# Four-leg_robot.net
KiCad netlist of a schematic drawn in Altium Designer
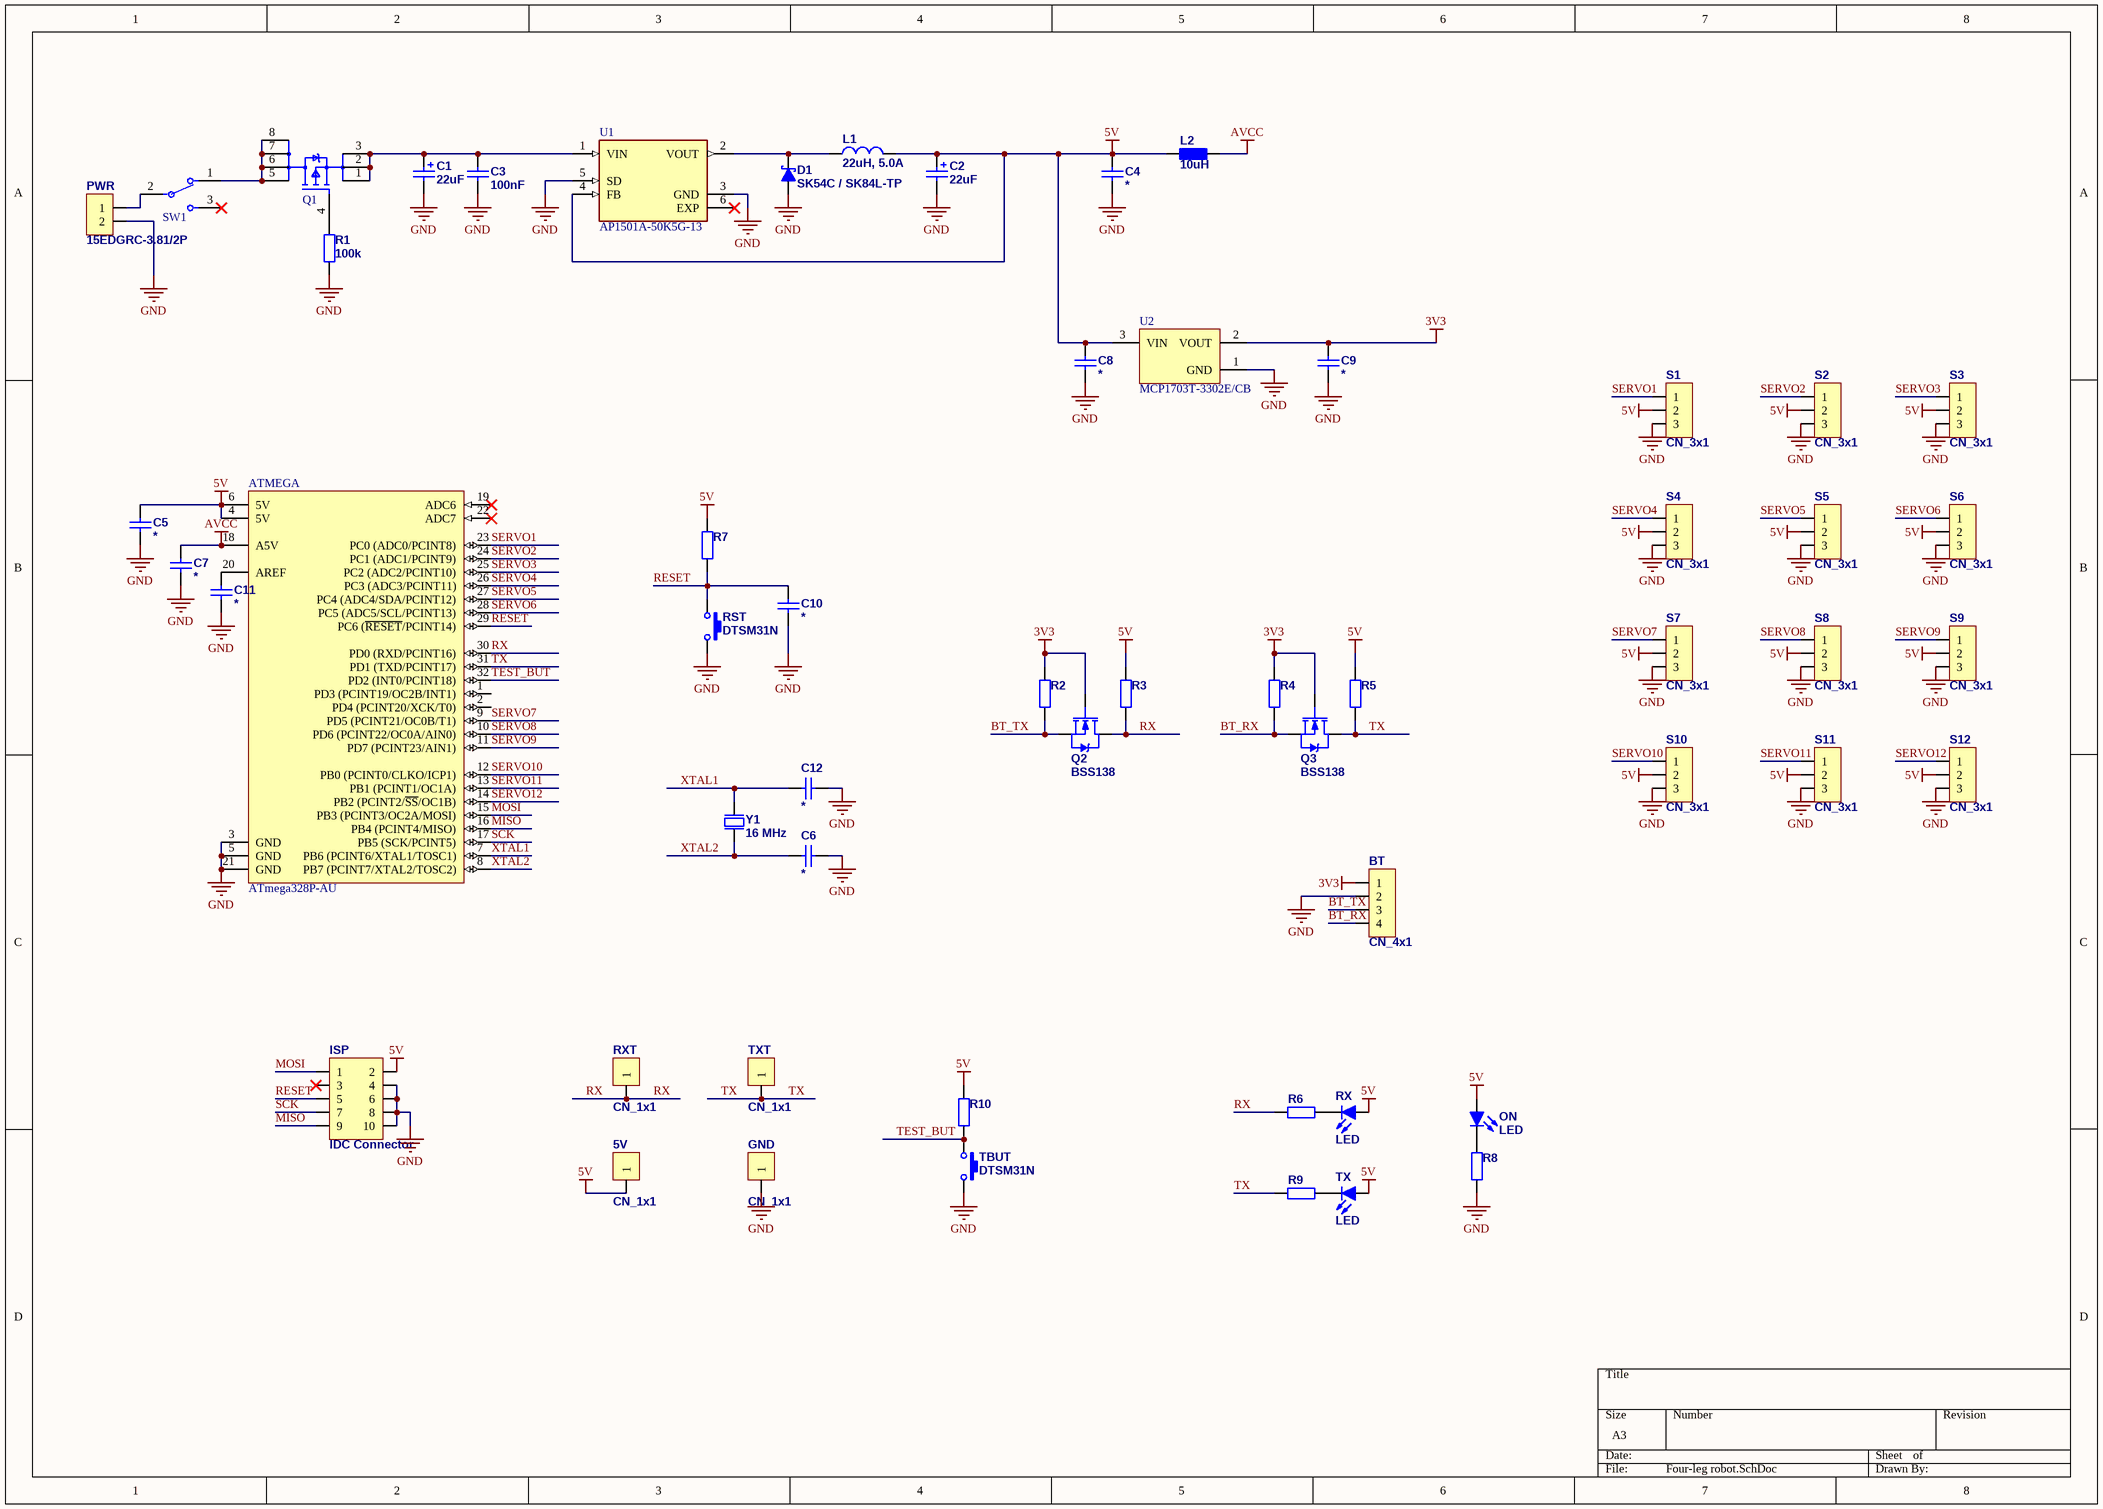
[diagram p0: Four-leg robot.SchDoc]

(export (version "E")
  (design (tool "Eeschema 10.0.6"))
  (components
    (comp (ref "5V") (value "CN_1x1") (footprint "GP_1x1") (libsource (lib "goldpin_male") (part "CN_1x1")))
    (comp (ref "ATMEGA")
      (value "ATmega328P-AU")
      (footprint "32A_N")
      (libsource (lib "Atmel Microcontroller megaAVR") (part "ATmega328P-AU"))
    )
    (comp (ref "BT")
      (value "CN_4x1")
      (footprint "GP_4x1_F")
      (libsource (lib "goldpin_female") (part "CN_4x1"))
    )
    (comp (ref "C1")
      (value "22uF")
      (footprint "SMDB")
      (description "Polarized Tantalum Capacitor")
      (libsource (lib "capacitors") (part "Cap Pol Tant"))
    )
    (comp (ref "C2")
      (value "22uF")
      (footprint "SMDB")
      (description "Polarized Tantalum Capacitor")
      (libsource (lib "capacitors") (part "Cap Pol Tant"))
    )
    (comp (ref "C3")
      (value "100nF")
      (footprint "C0805")
      (description "Capacitor")
      (libsource (lib "capacitors") (part "Cap"))
    )
    (comp (ref "C4")
      (value "*")
      (footprint "C0805")
      (description "Capacitor")
      (fields (field (name "ALTIUM_VALUE") "*"))
      (libsource (lib "capacitors") (part "Cap"))
    )
    (comp (ref "C5")
      (value "*")
      (footprint "C0805")
      (description "Capacitor")
      (fields (field (name "ALTIUM_VALUE") "*"))
      (libsource (lib "capacitors") (part "Cap"))
    )
    (comp (ref "C6")
      (value "*")
      (footprint "C0805")
      (description "Capacitor")
      (fields (field (name "ALTIUM_VALUE") "*"))
      (libsource (lib "capacitors") (part "Cap"))
    )
    (comp (ref "C7")
      (value "*")
      (footprint "C0805")
      (description "Capacitor")
      (fields (field (name "ALTIUM_VALUE") "*"))
      (libsource (lib "capacitors") (part "Cap"))
    )
    (comp (ref "C8")
      (value "*")
      (footprint "C0805")
      (description "Capacitor")
      (fields (field (name "ALTIUM_VALUE") "*"))
      (libsource (lib "capacitors") (part "Cap"))
    )
    (comp (ref "C9")
      (value "*")
      (footprint "C0805")
      (description "Capacitor")
      (fields (field (name "ALTIUM_VALUE") "*"))
      (libsource (lib "capacitors") (part "Cap"))
    )
    (comp (ref "C10")
      (value "*")
      (footprint "C0805")
      (description "Capacitor")
      (fields (field (name "ALTIUM_VALUE") "*"))
      (libsource (lib "capacitors") (part "Cap"))
    )
    (comp (ref "C11")
      (value "*")
      (footprint "C0805")
      (description "Capacitor")
      (fields (field (name "ALTIUM_VALUE") "*"))
      (libsource (lib "capacitors") (part "Cap"))
    )
    (comp (ref "C12")
      (value "*")
      (footprint "C0805")
      (description "Capacitor")
      (fields (field (name "ALTIUM_VALUE") "*"))
      (libsource (lib "capacitors") (part "Cap"))
    )
    (comp (ref "D1")
      (value "SK54C / SK84L-TP")
      (footprint "SMC")
      (description "Schottky Diode: 40V, 5A")
      (libsource (lib "diodes_schottky") (part "SK54C"))
    )
    (comp (ref "GND") (value "CN_1x1") (footprint "GP_1x1") (libsource (lib "goldpin_male") (part "CN_1x1")))
    (comp (ref "ISP") (value "IDC Connector") (footprint "IDC10") (libsource (lib "idc") (part "CN_5x2")))
    (comp (ref "L1")
      (value "22uH, 5.0A")
      (footprint "DE1209")
      (description "DE1209-22")
      (libsource (lib "inductors") (part "DE1209-22"))
    )
    (comp (ref "L2")
      (value "10uH")
      (footprint "L0805")
      (description "Inductor")
      (libsource (lib "inductors") (part "Ind2"))
    )
    (comp (ref "ON")
      (value "LED")
      (footprint "LED0805G")
      (description "Typical RED, GREEN, YELLOW, AMBER GaAs LED")
      (libsource (lib "leds") (part "LED"))
    )
    (comp (ref "PWR")
      (value "15EDGRC-3.81/2P")
      (footprint "15EDGRC-3.81/2P_WO_CN")
      (description "Degson 7A, 250V, 2 Pole Plug-in Terminal Block")
      (libsource (lib "terminal_blocks") (part "15EDGRC-3.81/2P"))
    )
    (comp (ref "Q1")
      (value "IRF7425PBF")
      (footprint "Infineon_PG-DSO-8_MFG")
      (libsource (lib "Trans_Infineon_IRF7425PBF_eec") (part "IRF7425PBF"))
    )
    (comp (ref "Q2")
      (value "BSS138")
      (footprint "SOT-23")
      (description "N-Channel Enhancement Mode Vertical DMOS FET")
      (fields (field (name "PUBLISHER") "Altium Limited"))
      (libsource (lib "transistors_mos") (part "BSS138"))
    )
    (comp (ref "Q3")
      (value "BSS138")
      (footprint "SOT-23")
      (description "N-Channel Enhancement Mode Vertical DMOS FET")
      (fields (field (name "PUBLISHER") "Altium Limited"))
      (libsource (lib "transistors_mos") (part "BSS138"))
    )
    (comp (ref "R1")
      (value "100k")
      (footprint "R0805")
      (description "Resistor")
      (libsource (lib "resistors") (part "Res"))
    )
    (comp (ref "R2")
      (value "~")
      (footprint "R0805")
      (description "Resistor")
      (libsource (lib "resistors") (part "Res"))
    )
    (comp (ref "R3")
      (value "~")
      (footprint "R0805")
      (description "Resistor")
      (libsource (lib "resistors") (part "Res"))
    )
    (comp (ref "R4")
      (value "~")
      (footprint "R0805")
      (description "Resistor")
      (libsource (lib "resistors") (part "Res"))
    )
    (comp (ref "R5")
      (value "~")
      (footprint "R0805")
      (description "Resistor")
      (libsource (lib "resistors") (part "Res"))
    )
    (comp (ref "R6")
      (value "~")
      (footprint "R0805")
      (description "Resistor")
      (libsource (lib "") (part "Res_1"))
    )
    (comp (ref "R7")
      (value "~")
      (footprint "R0805")
      (description "Resistor")
      (libsource (lib "resistors") (part "Res"))
    )
    (comp (ref "R8")
      (value "~")
      (footprint "R0805")
      (description "Resistor")
      (libsource (lib "resistors") (part "Res"))
    )
    (comp (ref "R9")
      (value "~")
      (footprint "R0805")
      (description "Resistor")
      (libsource (lib "") (part "Res_1"))
    )
    (comp (ref "R10")
      (value "~")
      (footprint "R0805")
      (description "Resistor")
      (libsource (lib "resistors") (part "Res"))
    )
    (comp (ref "RST")
      (value "DTSM31N")
      (footprint "DTSM-3")
      (description "DIPTRONICS 6x3,5mm SMD Tactile SPST-NO Switch")
      (libsource (lib "microswitches") (part "DTSM31N"))
    )
    (comp (ref "RX")
      (value "LED")
      (footprint "LED0805G")
      (description "Typical RED, GREEN, YELLOW, AMBER GaAs LED")
      (libsource (lib "leds") (part "LED"))
    )
    (comp (ref "RXT") (value "CN_1x1") (footprint "GP_1x1") (libsource (lib "goldpin_male") (part "CN_1x1")))
    (comp (ref "S1") (value "CN_3x1") (footprint "GP_3x1") (libsource (lib "goldpin_male") (part "CN_3x1")))
    (comp (ref "S2") (value "CN_3x1") (footprint "GP_3x1") (libsource (lib "goldpin_male") (part "CN_3x1")))
    (comp (ref "S3") (value "CN_3x1") (footprint "GP_3x1") (libsource (lib "goldpin_male") (part "CN_3x1")))
    (comp (ref "S4") (value "CN_3x1") (footprint "GP_3x1") (libsource (lib "goldpin_male") (part "CN_3x1")))
    (comp (ref "S5") (value "CN_3x1") (footprint "GP_3x1") (libsource (lib "goldpin_male") (part "CN_3x1")))
    (comp (ref "S6") (value "CN_3x1") (footprint "GP_3x1") (libsource (lib "goldpin_male") (part "CN_3x1")))
    (comp (ref "S7") (value "CN_3x1") (footprint "GP_3x1") (libsource (lib "goldpin_male") (part "CN_3x1")))
    (comp (ref "S8") (value "CN_3x1") (footprint "GP_3x1") (libsource (lib "goldpin_male") (part "CN_3x1")))
    (comp (ref "S9") (value "CN_3x1") (footprint "GP_3x1") (libsource (lib "goldpin_male") (part "CN_3x1")))
    (comp (ref "S10") (value "CN_3x1") (footprint "GP_3x1") (libsource (lib "goldpin_male") (part "CN_3x1")))
    (comp (ref "S11") (value "CN_3x1") (footprint "GP_3x1") (libsource (lib "goldpin_male") (part "CN_3x1")))
    (comp (ref "S12") (value "CN_3x1") (footprint "GP_3x1") (libsource (lib "goldpin_male") (part "CN_3x1")))
    (comp (ref "SW1")
      (value "Switch_C&K_1101M2S3CQE2_eec")
      (footprint "C&K_1101M2S3CQE2_0")
      (description "SWITCH SLIDE SPDT 6A 120V")
      (fields (field (name "PART NUMBER") "1101M2S3CQE2") (field (name "MANUFACTURER") "C&K"))
      (libsource (lib "Switch_C&K_1101M2S3CQE2_eec") (part "Switch_C&K_1101M2S3CQE2_eec"))
    )
    (comp (ref "TBUT")
      (value "DTSM31N")
      (footprint "DTSM-3")
      (description "DIPTRONICS 6x3,5mm SMD Tactile SPST-NO Switch")
      (libsource (lib "microswitches") (part "DTSM31N"))
    )
    (comp (ref "TX")
      (value "LED")
      (footprint "LED0805G")
      (description "Typical RED, GREEN, YELLOW, AMBER GaAs LED")
      (libsource (lib "leds") (part "LED"))
    )
    (comp (ref "TXT") (value "CN_1x1") (footprint "GP_1x1") (libsource (lib "goldpin_male") (part "CN_1x1")))
    (comp (ref "U1")
      (value "AP1501A-50K5G-13")
      (footprint "TO-263-5:TO-263-5")
      (description "Voltage stabiliser; PMIC; 5A; TO263-5; SMD; buck; -20Ã·85Â°C; 800pcs.")
      (libsource (lib "AP1501A-33K5G-13") (part "AP1501A-33K5G-13"))
    )
    (comp (ref "U2")
      (value "MCP1703T-3302E/CB")
      (footprint "SOT-23")
      (libsource (lib "Microchip_MCP1703T_3302E_CB") (part "MCP1703T-3302E/CB"))
    )
    (comp (ref "Y1")
      (value "16 MHz")
      (footprint "HC49-S")
      (description "Crystal Oscillator")
      (libsource (lib "quartz_crystals_and_filters") (part "XTAL_2PIN"))
    )
  )
  (nets
    (net (code "1") (name "/BT_RX") (class "Default")
      (node (ref "BT") (pin "4") (pinfunction "4_4") (pintype "passive"))
      (node (ref "Q3") (pin "2") (pinfunction "S_2") (pintype "passive"))
      (node (ref "R4") (pin "1") (pinfunction "1_1") (pintype "passive"))
    )
    (net (code "2") (name "/BT_TX") (class "Default")
      (node (ref "BT") (pin "3") (pinfunction "3_3") (pintype "passive"))
      (node (ref "Q2") (pin "2") (pinfunction "S_2") (pintype "passive"))
      (node (ref "R2") (pin "1") (pinfunction "1_1") (pintype "passive"))
    )
    (net (code "3") (name "/MISO") (class "Default")
      (node (ref "ATMEGA") (pin "16") (pinfunction "PB4_(PCINT4/MISO)_16") (pintype "bidirectional"))
      (node (ref "ISP") (pin "9") (pinfunction "9_9") (pintype "passive"))
    )
    (net (code "4") (name "/MOSI") (class "Default")
      (node (ref "ATMEGA") (pin "15") (pinfunction "PB3_(PCINT3/OC2A/MOSI)_15") (pintype "bidirectional"))
      (node (ref "ISP") (pin "1") (pinfunction "1_1") (pintype "passive"))
    )
    (net (code "5") (name "/RESET") (class "Default")
      (node (ref "ATMEGA") (pin "29") (pinfunction "PC6_(~{RESET}/PCINT14)_29") (pintype "bidirectional"))
      (node (ref "C10") (pin "2") (pinfunction "2_2") (pintype "passive"))
      (node (ref "ISP") (pin "5") (pinfunction "5_5") (pintype "passive"))
      (node (ref "R7") (pin "1") (pinfunction "1_1") (pintype "passive"))
      (node (ref "RST") (pin "1") (pinfunction "1_1") (pintype "passive"))
    )
    (net (code "6") (name "/RX") (class "Default")
      (node (ref "ATMEGA") (pin "30") (pinfunction "PD0_(RXD/PCINT16)_30") (pintype "bidirectional"))
      (node (ref "Q2") (pin "3") (pinfunction "D_3") (pintype "passive"))
      (node (ref "R3") (pin "1") (pinfunction "1_1") (pintype "passive"))
      (node (ref "R6") (pin "1") (pinfunction "1_1") (pintype "passive"))
      (node (ref "RXT") (pin "1") (pinfunction "1_1") (pintype "passive"))
    )
    (net (code "7") (name "/SCK") (class "Default")
      (node (ref "ATMEGA") (pin "17") (pinfunction "PB5_(SCK/PCINT5)_17") (pintype "bidirectional"))
      (node (ref "ISP") (pin "7") (pinfunction "7_7") (pintype "passive"))
    )
    (net (code "8") (name "/SERVO1") (class "Default")
      (node (ref "ATMEGA") (pin "23") (pinfunction "PC0_(ADC0/PCINT8)_23") (pintype "bidirectional"))
      (node (ref "S1") (pin "1") (pinfunction "1_1") (pintype "passive"))
    )
    (net (code "9") (name "/SERVO2") (class "Default")
      (node (ref "ATMEGA") (pin "24") (pinfunction "PC1_(ADC1/PCINT9)_24") (pintype "bidirectional"))
      (node (ref "S2") (pin "1") (pinfunction "1_1") (pintype "passive"))
    )
    (net (code "10") (name "/SERVO3") (class "Default")
      (node (ref "ATMEGA") (pin "25") (pinfunction "PC2_(ADC2/PCINT10)_25") (pintype "bidirectional"))
      (node (ref "S3") (pin "1") (pinfunction "1_1") (pintype "passive"))
    )
    (net (code "11") (name "/SERVO4") (class "Default")
      (node (ref "ATMEGA") (pin "26") (pinfunction "PC3_(ADC3/PCINT11)_26") (pintype "bidirectional"))
      (node (ref "S4") (pin "1") (pinfunction "1_1") (pintype "passive"))
    )
    (net (code "12") (name "/SERVO5") (class "Default")
      (node (ref "ATMEGA") (pin "27") (pinfunction "PC4_(ADC4/SDA/PCINT12)_27") (pintype "bidirectional"))
      (node (ref "S5") (pin "1") (pinfunction "1_1") (pintype "passive"))
    )
    (net (code "13") (name "/SERVO6") (class "Default")
      (node (ref "ATMEGA") (pin "28") (pinfunction "PC5_(ADC5/SCL/PCINT13)_28") (pintype "bidirectional"))
      (node (ref "S6") (pin "1") (pinfunction "1_1") (pintype "passive"))
    )
    (net (code "14") (name "/SERVO7") (class "Default")
      (node (ref "ATMEGA") (pin "9") (pinfunction "PD5_(PCINT21/OC0B/T1)_9") (pintype "bidirectional"))
      (node (ref "S7") (pin "1") (pinfunction "1_1") (pintype "passive"))
    )
    (net (code "15") (name "/SERVO8") (class "Default")
      (node (ref "ATMEGA") (pin "10") (pinfunction "PD6_(PCINT22/OC0A/AIN0)_10") (pintype "bidirectional"))
      (node (ref "S8") (pin "1") (pinfunction "1_1") (pintype "passive"))
    )
    (net (code "16") (name "/SERVO9") (class "Default")
      (node (ref "ATMEGA") (pin "11") (pinfunction "PD7_(PCINT23/AIN1)_11") (pintype "bidirectional"))
      (node (ref "S9") (pin "1") (pinfunction "1_1") (pintype "passive"))
    )
    (net (code "17") (name "/SERVO10") (class "Default")
      (node (ref "ATMEGA") (pin "12") (pinfunction "PB0_(PCINT0/CLKO/ICP1)_12") (pintype "bidirectional"))
      (node (ref "S10") (pin "1") (pinfunction "1_1") (pintype "passive"))
    )
    (net (code "18") (name "/SERVO11") (class "Default")
      (node (ref "ATMEGA") (pin "13") (pinfunction "PB1_(PCINT1/OC1A)_13") (pintype "bidirectional"))
      (node (ref "S11") (pin "1") (pinfunction "1_1") (pintype "passive"))
    )
    (net (code "19") (name "/SERVO12") (class "Default")
      (node (ref "ATMEGA") (pin "14") (pinfunction "PB2_(PCINT2/~{SS}/OC1B)_14") (pintype "bidirectional"))
      (node (ref "S12") (pin "1") (pinfunction "1_1") (pintype "passive"))
    )
    (net (code "20") (name "/TEST_BUT") (class "Default")
      (node (ref "ATMEGA") (pin "32") (pinfunction "PD2_(INT0/PCINT18)_32") (pintype "bidirectional"))
      (node (ref "R10") (pin "1") (pinfunction "1_1") (pintype "passive"))
      (node (ref "TBUT") (pin "1") (pinfunction "1_1") (pintype "passive"))
    )
    (net (code "21") (name "/TX") (class "Default")
      (node (ref "ATMEGA") (pin "31") (pinfunction "PD1_(TXD/PCINT17)_31") (pintype "bidirectional"))
      (node (ref "Q3") (pin "3") (pinfunction "D_3") (pintype "passive"))
      (node (ref "R5") (pin "1") (pinfunction "1_1") (pintype "passive"))
      (node (ref "R9") (pin "1") (pinfunction "1_1") (pintype "passive"))
      (node (ref "TXT") (pin "1") (pinfunction "1_1") (pintype "passive"))
    )
    (net (code "22") (name "/XTAL1") (class "Default")
      (node (ref "ATMEGA") (pin "7") (pinfunction "PB6_(PCINT6/XTAL1/TOSC1)_7") (pintype "bidirectional"))
      (node (ref "C12") (pin "2") (pinfunction "2_2") (pintype "passive"))
      (node (ref "Y1") (pin "2") (pinfunction "OSC2_2") (pintype "passive"))
    )
    (net (code "23") (name "/XTAL2") (class "Default")
      (node (ref "ATMEGA") (pin "8") (pinfunction "PB7_(PCINT7/XTAL2/TOSC2)_8") (pintype "bidirectional"))
      (node (ref "C6") (pin "2") (pinfunction "2_2") (pintype "passive"))
      (node (ref "Y1") (pin "1") (pinfunction "OSC1_1") (pintype "passive"))
    )
    (net (code "24") (name "3V3") (class "Default")
      (node (ref "BT") (pin "1") (pinfunction "1_1") (pintype "passive"))
      (node (ref "C9") (pin "2") (pinfunction "2_2") (pintype "passive"))
      (node (ref "Q2") (pin "1") (pinfunction "G_1") (pintype "passive"))
      (node (ref "Q3") (pin "1") (pinfunction "G_1") (pintype "passive"))
      (node (ref "R2") (pin "2") (pinfunction "2_2") (pintype "passive"))
      (node (ref "R4") (pin "2") (pinfunction "2_2") (pintype "passive"))
      (node (ref "U2") (pin "2") (pinfunction "VOUT_2") (pintype "power_in"))
    )
    (net (code "25") (name "5V") (class "Default")
      (node (ref "5V") (pin "1") (pinfunction "1_1") (pintype "passive"))
      (node (ref "ATMEGA") (pin "4") (pinfunction "5V_4") (pintype "power_in"))
      (node (ref "ATMEGA") (pin "6") (pinfunction "5V_6") (pintype "power_in"))
      (node (ref "C2") (pin "1") (pinfunction "1_1") (pintype "passive"))
      (node (ref "C4") (pin "2") (pinfunction "2_2") (pintype "passive"))
      (node (ref "C5") (pin "2") (pinfunction "2_2") (pintype "passive"))
      (node (ref "C8") (pin "2") (pinfunction "2_2") (pintype "passive"))
      (node (ref "ISP") (pin "2") (pinfunction "2_2") (pintype "passive"))
      (node (ref "L1") (pin "2") (pinfunction "2_2") (pintype "passive"))
      (node (ref "L2") (pin "1") (pinfunction "1_1") (pintype "passive"))
      (node (ref "ON") (pin "1") (pinfunction "A_1") (pintype "passive"))
      (node (ref "R10") (pin "2") (pinfunction "2_2") (pintype "passive"))
      (node (ref "R3") (pin "2") (pinfunction "2_2") (pintype "passive"))
      (node (ref "R5") (pin "2") (pinfunction "2_2") (pintype "passive"))
      (node (ref "R7") (pin "2") (pinfunction "2_2") (pintype "passive"))
      (node (ref "RX") (pin "1") (pinfunction "A_1") (pintype "passive"))
      (node (ref "S1") (pin "2") (pinfunction "2_2") (pintype "passive"))
      (node (ref "S10") (pin "2") (pinfunction "2_2") (pintype "passive"))
      (node (ref "S11") (pin "2") (pinfunction "2_2") (pintype "passive"))
      (node (ref "S12") (pin "2") (pinfunction "2_2") (pintype "passive"))
      (node (ref "S2") (pin "2") (pinfunction "2_2") (pintype "passive"))
      (node (ref "S3") (pin "2") (pinfunction "2_2") (pintype "passive"))
      (node (ref "S4") (pin "2") (pinfunction "2_2") (pintype "passive"))
      (node (ref "S5") (pin "2") (pinfunction "2_2") (pintype "passive"))
      (node (ref "S6") (pin "2") (pinfunction "2_2") (pintype "passive"))
      (node (ref "S7") (pin "2") (pinfunction "2_2") (pintype "passive"))
      (node (ref "S8") (pin "2") (pinfunction "2_2") (pintype "passive"))
      (node (ref "S9") (pin "2") (pinfunction "2_2") (pintype "passive"))
      (node (ref "TX") (pin "1") (pinfunction "A_1") (pintype "passive"))
      (node (ref "U1") (pin "4") (pinfunction "FB_4") (pintype "input"))
      (node (ref "U2") (pin "3") (pinfunction "VIN_3") (pintype "power_in"))
    )
    (net (code "26") (name "AVCC") (class "Default")
      (node (ref "ATMEGA") (pin "18") (pinfunction "A5V_18") (pintype "power_in"))
      (node (ref "C7") (pin "2") (pinfunction "2_2") (pintype "passive"))
      (node (ref "L2") (pin "2") (pinfunction "2_2") (pintype "passive"))
    )
    (net (code "27") (name "GND") (class "Default")
      (node (ref "ATMEGA") (pin "21") (pinfunction "GND_21") (pintype "power_in"))
      (node (ref "ATMEGA") (pin "3") (pinfunction "GND_3") (pintype "power_in"))
      (node (ref "ATMEGA") (pin "5") (pinfunction "GND_5") (pintype "power_in"))
      (node (ref "BT") (pin "2") (pinfunction "2_2") (pintype "passive"))
      (node (ref "C1") (pin "2") (pinfunction "2_2") (pintype "passive"))
      (node (ref "C10") (pin "1") (pinfunction "1_1") (pintype "passive"))
      (node (ref "C11") (pin "1") (pinfunction "1_1") (pintype "passive"))
      (node (ref "C12") (pin "1") (pinfunction "1_1") (pintype "passive"))
      (node (ref "C2") (pin "2") (pinfunction "2_2") (pintype "passive"))
      (node (ref "C3") (pin "1") (pinfunction "1_1") (pintype "passive"))
      (node (ref "C4") (pin "1") (pinfunction "1_1") (pintype "passive"))
      (node (ref "C5") (pin "1") (pinfunction "1_1") (pintype "passive"))
      (node (ref "C6") (pin "1") (pinfunction "1_1") (pintype "passive"))
      (node (ref "C7") (pin "1") (pinfunction "1_1") (pintype "passive"))
      (node (ref "C8") (pin "1") (pinfunction "1_1") (pintype "passive"))
      (node (ref "C9") (pin "1") (pinfunction "1_1") (pintype "passive"))
      (node (ref "D1") (pin "1") (pinfunction "A_1") (pintype "passive"))
      (node (ref "GND") (pin "1") (pinfunction "1_1") (pintype "passive"))
      (node (ref "ISP") (pin "10") (pinfunction "10_10") (pintype "passive"))
      (node (ref "ISP") (pin "4") (pinfunction "4_4") (pintype "passive"))
      (node (ref "ISP") (pin "6") (pinfunction "6_6") (pintype "passive"))
      (node (ref "ISP") (pin "8") (pinfunction "8_8") (pintype "passive"))
      (node (ref "PWR") (pin "2") (pinfunction "2_2") (pintype "passive"))
      (node (ref "R1") (pin "1") (pinfunction "1_1") (pintype "passive"))
      (node (ref "R8") (pin "1") (pinfunction "1_1") (pintype "passive"))
      (node (ref "RST") (pin "2") (pinfunction "2_2") (pintype "passive"))
      (node (ref "S1") (pin "3") (pinfunction "3_3") (pintype "passive"))
      (node (ref "S10") (pin "3") (pinfunction "3_3") (pintype "passive"))
      (node (ref "S11") (pin "3") (pinfunction "3_3") (pintype "passive"))
      (node (ref "S12") (pin "3") (pinfunction "3_3") (pintype "passive"))
      (node (ref "S2") (pin "3") (pinfunction "3_3") (pintype "passive"))
      (node (ref "S3") (pin "3") (pinfunction "3_3") (pintype "passive"))
      (node (ref "S4") (pin "3") (pinfunction "3_3") (pintype "passive"))
      (node (ref "S5") (pin "3") (pinfunction "3_3") (pintype "passive"))
      (node (ref "S6") (pin "3") (pinfunction "3_3") (pintype "passive"))
      (node (ref "S7") (pin "3") (pinfunction "3_3") (pintype "passive"))
      (node (ref "S8") (pin "3") (pinfunction "3_3") (pintype "passive"))
      (node (ref "S9") (pin "3") (pinfunction "3_3") (pintype "passive"))
      (node (ref "TBUT") (pin "2") (pinfunction "2_2") (pintype "passive"))
      (node (ref "U1") (pin "3") (pinfunction "GND_3") (pintype "power_in"))
      (node (ref "U1") (pin "5") (pinfunction "SD_5") (pintype "input"))
      (node (ref "U2") (pin "1") (pinfunction "GND_1") (pintype "power_in"))
    )
    (net (code "28") (name "Net-(ATMEGA-AREF)") (class "Default")
      (node (ref "ATMEGA") (pin "20") (pinfunction "AREF_20") (pintype "passive"))
      (node (ref "C11") (pin "2") (pinfunction "2_2") (pintype "passive"))
    )
    (net (code "29") (name "Net-(D1-K)") (class "Default")
      (node (ref "D1") (pin "2") (pinfunction "K_2") (pintype "passive"))
      (node (ref "L1") (pin "1") (pinfunction "1_1") (pintype "passive"))
      (node (ref "U1") (pin "2") (pinfunction "VOUT_2") (pintype "output"))
    )
    (net (code "30") (name "Net-(ON-K)") (class "Default")
      (node (ref "ON") (pin "2") (pinfunction "K_2") (pintype "passive"))
      (node (ref "R8") (pin "2") (pinfunction "2_2") (pintype "passive"))
    )
    (net (code "31") (name "Net-(Q1-D-Pad5)") (class "Default")
      (node (ref "Q1") (pin "5") (pinfunction "D_5") (pintype "passive"))
      (node (ref "Q1") (pin "6") (pinfunction "D_6") (pintype "passive"))
      (node (ref "Q1") (pin "7") (pinfunction "D_7") (pintype "passive"))
      (node (ref "Q1") (pin "8") (pinfunction "D_8") (pintype "passive"))
      (node (ref "SW1") (pin "1") (pinfunction "1_1") (pintype "passive"))
    )
    (net (code "32") (name "Net-(Q1-G)") (class "Default")
      (node (ref "Q1") (pin "4") (pinfunction "G_4") (pintype "passive"))
      (node (ref "R1") (pin "2") (pinfunction "2_2") (pintype "passive"))
    )
    (net (code "33") (name "Net-(RX-K)") (class "Default")
      (node (ref "R6") (pin "2") (pinfunction "2_2") (pintype "passive"))
      (node (ref "RX") (pin "2") (pinfunction "K_2") (pintype "passive"))
    )
    (net (code "34") (name "Net-(SW1-COM)") (class "Default")
      (node (ref "PWR") (pin "1") (pinfunction "1_1") (pintype "passive"))
      (node (ref "SW1") (pin "2") (pinfunction "COM_2") (pintype "passive"))
    )
    (net (code "35") (name "Net-(TX-K)") (class "Default")
      (node (ref "R9") (pin "2") (pinfunction "2_2") (pintype "passive"))
      (node (ref "TX") (pin "2") (pinfunction "K_2") (pintype "passive"))
    )
    (net (code "36") (name "Net-(U1-VIN)") (class "Default")
      (node (ref "C1") (pin "1") (pinfunction "1_1") (pintype "passive"))
      (node (ref "C3") (pin "2") (pinfunction "2_2") (pintype "passive"))
      (node (ref "Q1") (pin "1") (pinfunction "S_1") (pintype "passive"))
      (node (ref "Q1") (pin "2") (pinfunction "S_2") (pintype "passive"))
      (node (ref "Q1") (pin "3") (pinfunction "S_3") (pintype "passive"))
      (node (ref "U1") (pin "1") (pinfunction "VIN_1") (pintype "input"))
    )
    (net (code "37") (name "unconnected-(ATMEGA-ADC6-Pad19)") (class "Default")
      (node (ref "ATMEGA") (pin "19") (pinfunction "ADC6_19") (pintype "input+no_connect"))
    )
    (net (code "38") (name "unconnected-(ATMEGA-ADC7-Pad22)") (class "Default")
      (node (ref "ATMEGA") (pin "22") (pinfunction "ADC7_22") (pintype "input+no_connect"))
    )
    (net (code "39") (name "unconnected-(ATMEGA-PD3_(PCINT19{slash}OC2B{slash}INT1)-Pad1)") (class "Default")
      (node (ref "ATMEGA") (pin "1") (pinfunction "PD3_(PCINT19/OC2B/INT1)_1") (pintype "bidirectional"))
    )
    (net (code "40") (name "unconnected-(ATMEGA-PD4_(PCINT20{slash}XCK{slash}T0)-Pad2)") (class "Default")
      (node (ref "ATMEGA") (pin "2") (pinfunction "PD4_(PCINT20/XCK/T0)_2") (pintype "bidirectional"))
    )
    (net (code "41") (name "unconnected-(ISP-Pad3)") (class "Default")
      (node (ref "ISP") (pin "3") (pinfunction "3_3") (pintype "passive+no_connect"))
    )
    (net (code "42") (name "unconnected-(SW1-Pad3)") (class "Default")
      (node (ref "SW1") (pin "3") (pinfunction "3_3") (pintype "passive+no_connect"))
    )
    (net (code "43") (name "unconnected-(U1-EXP-Pad6)") (class "Default")
      (node (ref "U1") (pin "6") (pinfunction "EXP_6") (pintype "power_in+no_connect"))
    )
  )
)
